# counter_using_CD4026BE.net
KiCad netlist of a schematic drawn in Altium Designer
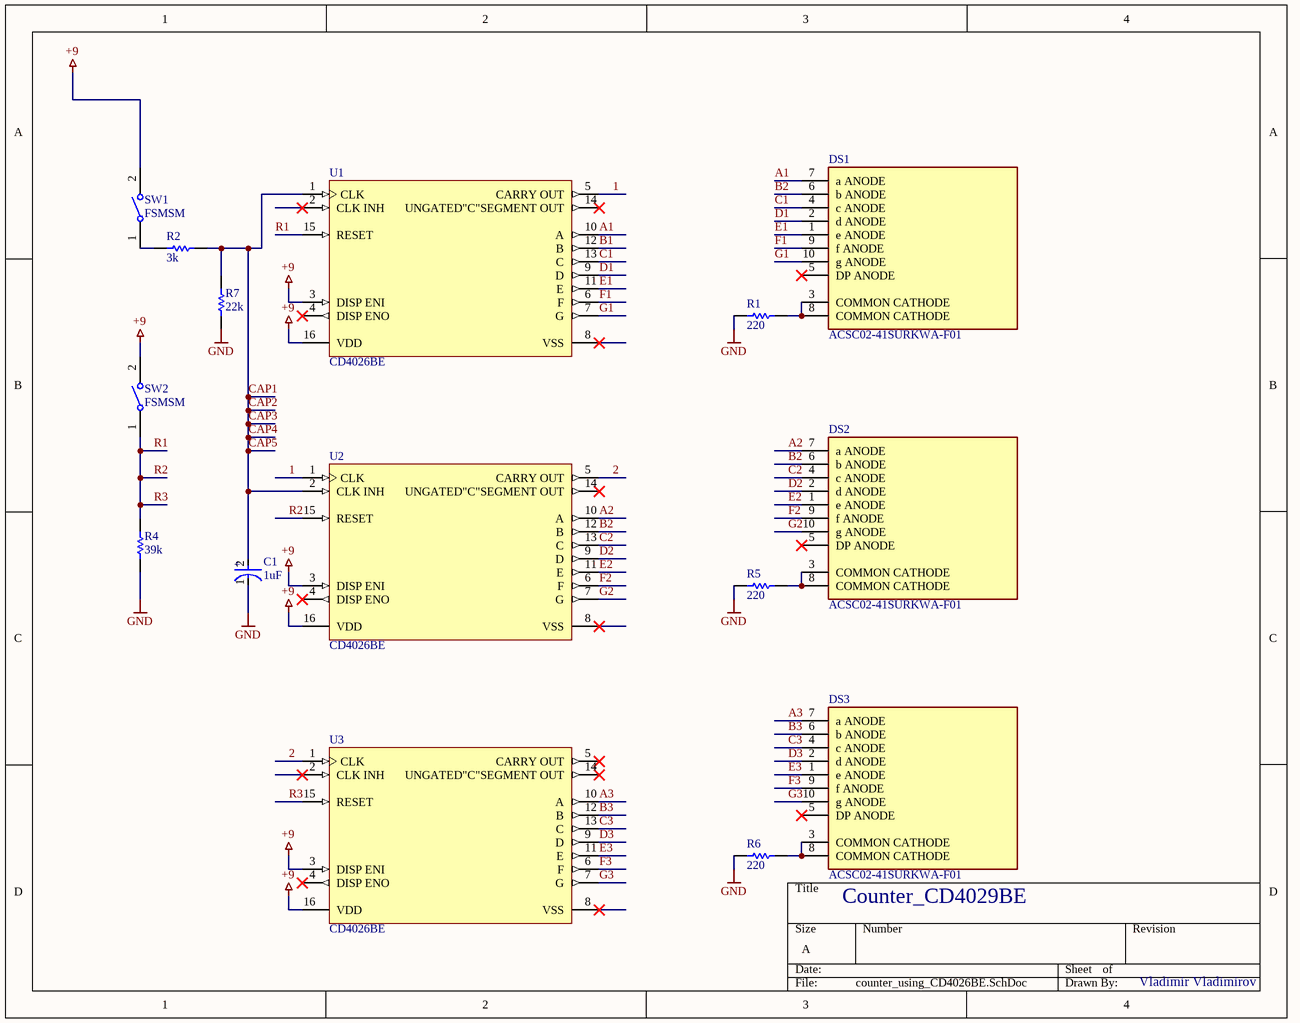
[diagram p0: counter_using_CD4026BE.SchDoc]

(export (version "E")
  (design (tool "Eeschema 10.0.6"))
  (components
    (comp (ref "C1")
      (value "1uF")
      (footprint "FP-FCB-MFG")
      (fields (field (name "TOLERANCE") "20%") (field (name "VOLTAGE") "50V"))
      (libsource (lib "Altium Content Vault") (part "a00bbbee19879c290e62620ae7e47b1"))
    )
    (comp (ref "DS1")
      (value "ACSC02-41SURKWA-F01")
      (footprint "FP-ACSC02-41SURKWA-F01-MFG")
      (description "DISPLAY 7-SEG 0.2\" SGL RED 10SMD")
      (libsource (lib "Altium Content Vault") (part "0e920bf6b93db43d611184977c40d65"))
    )
    (comp (ref "DS2")
      (value "ACSC02-41SURKWA-F01")
      (footprint "FP-ACSC02-41SURKWA-F01-MFG")
      (description "DISPLAY 7-SEG 0.2\" SGL RED 10SMD")
      (libsource (lib "Altium Content Vault") (part "0e920bf6b93db43d611184977c40d65"))
    )
    (comp (ref "DS3")
      (value "ACSC02-41SURKWA-F01")
      (footprint "FP-ACSC02-41SURKWA-F01-MFG")
      (description "DISPLAY 7-SEG 0.2\" SGL RED 10SMD")
      (libsource (lib "Altium Content Vault") (part "0e920bf6b93db43d611184977c40d65"))
    )
    (comp (ref "R1")
      (value "220")
      (footprint "RESC2013X70X40NL20T20")
      (fields (field (name "PART NUMBER") "ERJ6ENF2200V") (field (name "MANUFACTURER") "Panasonic"))
      (libsource (lib "Altium Content Vault") (part "RES"))
    )
    (comp (ref "R2")
      (value "3k")
      (footprint "RESC2013X70X40NL20T20")
      (fields (field (name "PART NUMBER") "ERJ6ENF2200V") (field (name "MANUFACTURER") "Panasonic"))
      (libsource (lib "Altium Content Vault") (part "RES"))
    )
    (comp (ref "R4")
      (value "39k")
      (footprint "RESC2013X70X40NL20T20")
      (fields (field (name "PART NUMBER") "ERJ6ENF2200V") (field (name "MANUFACTURER") "Panasonic"))
      (libsource (lib "Altium Content Vault") (part "RES"))
    )
    (comp (ref "R5")
      (value "220")
      (footprint "RESC2013X70X40NL20T20")
      (fields (field (name "PART NUMBER") "ERJ6ENF2200V") (field (name "MANUFACTURER") "Panasonic"))
      (libsource (lib "Altium Content Vault") (part "RES"))
    )
    (comp (ref "R6")
      (value "220")
      (footprint "RESC2013X70X40NL20T20")
      (fields (field (name "PART NUMBER") "ERJ6ENF2200V") (field (name "MANUFACTURER") "Panasonic"))
      (libsource (lib "Altium Content Vault") (part "RES"))
    )
    (comp (ref "R7")
      (value "22k")
      (footprint "RESC2013X70X40NL20T20")
      (fields (field (name "PART NUMBER") "ERJ6ENF2200V") (field (name "MANUFACTURER") "Panasonic"))
      (libsource (lib "Altium Content Vault") (part "RES"))
    )
    (comp (ref "SW1")
      (value "FSMSM")
      (footprint "TECO-FSMSM-2_V")
      (description "FSMSM Push Button Switch, 50 mA, -35 to 85 degC, 2-Pin SMD, RoHS, Bulk")
      (fields (field (name "MANUFACTURER") "TE Connectivity"))
      (libsource (lib "Altium Content Vault") (part "SW-SPST-2_C"))
    )
    (comp (ref "SW2")
      (value "FSMSM")
      (footprint "TECO-FSMSM-2_V")
      (description "FSMSM Push Button Switch, 50 mA, -35 to 85 degC, 2-Pin SMD, RoHS, Bulk")
      (fields (field (name "MANUFACTURER") "TE Connectivity"))
      (libsource (lib "Altium Content Vault") (part "SW-SPST-2_C"))
    )
    (comp (ref "U1")
      (value "CD4026BE")
      (footprint "N0016A")
      (fields
        (field (name "MANUFACTURER") "Texas Instruments")
        (field (name "GENERIC PART NUMBER") "CD4026B")
      )
      (libsource (lib "Altium Content Vault") (part "TI-CD4026B-16"))
    )
    (comp (ref "U2")
      (value "CD4026BE")
      (footprint "N0016A")
      (fields
        (field (name "MANUFACTURER") "Texas Instruments")
        (field (name "GENERIC PART NUMBER") "CD4026B")
      )
      (libsource (lib "Altium Content Vault") (part "TI-CD4026B-16"))
    )
    (comp (ref "U3")
      (value "CD4026BE")
      (footprint "N0016A")
      (fields
        (field (name "MANUFACTURER") "Texas Instruments")
        (field (name "GENERIC PART NUMBER") "CD4026B")
      )
      (libsource (lib "Altium Content Vault") (part "TI-CD4026B-16"))
    )
  )
  (nets
    (net (code "1") (name "+9") (class "Default")
      (node (ref "SW1") (pin "2") (pinfunction "2_2") (pintype "passive"))
      (node (ref "SW2") (pin "2") (pinfunction "2_2") (pintype "passive"))
      (node (ref "U1") (pin "16") (pinfunction "VDD_16") (pintype "power_in"))
      (node (ref "U1") (pin "3") (pinfunction "DISP_ENI_3") (pintype "input"))
      (node (ref "U2") (pin "16") (pinfunction "VDD_16") (pintype "power_in"))
      (node (ref "U2") (pin "3") (pinfunction "DISP_ENI_3") (pintype "input"))
      (node (ref "U3") (pin "16") (pinfunction "VDD_16") (pintype "power_in"))
      (node (ref "U3") (pin "3") (pinfunction "DISP_ENI_3") (pintype "input"))
    )
    (net (code "2") (name "/1") (class "Default")
      (node (ref "U1") (pin "5") (pinfunction "CARRY_OUT_5") (pintype "output"))
      (node (ref "U2") (pin "1") (pinfunction "CLK_1") (pintype "input"))
    )
    (net (code "3") (name "/2") (class "Default")
      (node (ref "U2") (pin "5") (pinfunction "CARRY_OUT_5") (pintype "output"))
      (node (ref "U3") (pin "1") (pinfunction "CLK_1") (pintype "input"))
    )
    (net (code "4") (name "/A1") (class "Default")
      (node (ref "DS1") (pin "7") (pinfunction "a_ANODE_7") (pintype "passive"))
      (node (ref "U1") (pin "10") (pinfunction "A_10") (pintype "output"))
    )
    (net (code "5") (name "/A2") (class "Default")
      (node (ref "DS2") (pin "7") (pinfunction "a_ANODE_7") (pintype "passive"))
      (node (ref "U2") (pin "10") (pinfunction "A_10") (pintype "output"))
    )
    (net (code "6") (name "/A3") (class "Default")
      (node (ref "DS3") (pin "7") (pinfunction "a_ANODE_7") (pintype "passive"))
      (node (ref "U3") (pin "10") (pinfunction "A_10") (pintype "output"))
    )
    (net (code "7") (name "/B1") (class "Default")
      (node (ref "U1") (pin "12") (pinfunction "B_12") (pintype "output"))
    )
    (net (code "8") (name "/B2") (class "Default")
      (node (ref "DS1") (pin "6") (pinfunction "b_ANODE_6") (pintype "passive"))
      (node (ref "DS2") (pin "6") (pinfunction "b_ANODE_6") (pintype "passive"))
      (node (ref "U2") (pin "12") (pinfunction "B_12") (pintype "output"))
    )
    (net (code "9") (name "/B3") (class "Default")
      (node (ref "DS3") (pin "6") (pinfunction "b_ANODE_6") (pintype "passive"))
      (node (ref "U3") (pin "12") (pinfunction "B_12") (pintype "output"))
    )
    (net (code "10") (name "/C1") (class "Default")
      (node (ref "DS1") (pin "4") (pinfunction "c_ANODE_4") (pintype "passive"))
      (node (ref "U1") (pin "13") (pinfunction "C_13") (pintype "output"))
    )
    (net (code "11") (name "/C2") (class "Default")
      (node (ref "DS2") (pin "4") (pinfunction "c_ANODE_4") (pintype "passive"))
      (node (ref "U2") (pin "13") (pinfunction "C_13") (pintype "output"))
    )
    (net (code "12") (name "/C3") (class "Default")
      (node (ref "DS3") (pin "4") (pinfunction "c_ANODE_4") (pintype "passive"))
      (node (ref "U3") (pin "13") (pinfunction "C_13") (pintype "output"))
    )
    (net (code "13") (name "/CAP1") (class "Default")
      (node (ref "C1") (pin "2") (pinfunction "A_2") (pintype "passive"))
      (node (ref "R2") (pin "2") (pinfunction "2_2") (pintype "passive"))
      (node (ref "R7") (pin "2") (pinfunction "2_2") (pintype "passive"))
      (node (ref "U1") (pin "1") (pinfunction "CLK_1") (pintype "input"))
      (node (ref "U2") (pin "2") (pinfunction "CLK_INH_2") (pintype "input"))
    )
    (net (code "14") (name "/D1") (class "Default")
      (node (ref "DS1") (pin "2") (pinfunction "d_ANODE_2") (pintype "passive"))
      (node (ref "U1") (pin "9") (pinfunction "D_9") (pintype "output"))
    )
    (net (code "15") (name "/D2") (class "Default")
      (node (ref "DS2") (pin "2") (pinfunction "d_ANODE_2") (pintype "passive"))
      (node (ref "U2") (pin "9") (pinfunction "D_9") (pintype "output"))
    )
    (net (code "16") (name "/D3") (class "Default")
      (node (ref "DS3") (pin "2") (pinfunction "d_ANODE_2") (pintype "passive"))
      (node (ref "U3") (pin "9") (pinfunction "D_9") (pintype "output"))
    )
    (net (code "17") (name "/E1") (class "Default")
      (node (ref "DS1") (pin "1") (pinfunction "e_ANODE_1") (pintype "passive"))
      (node (ref "U1") (pin "11") (pinfunction "E_11") (pintype "output"))
    )
    (net (code "18") (name "/E2") (class "Default")
      (node (ref "DS2") (pin "1") (pinfunction "e_ANODE_1") (pintype "passive"))
      (node (ref "U2") (pin "11") (pinfunction "E_11") (pintype "output"))
    )
    (net (code "19") (name "/E3") (class "Default")
      (node (ref "DS3") (pin "1") (pinfunction "e_ANODE_1") (pintype "passive"))
      (node (ref "U3") (pin "11") (pinfunction "E_11") (pintype "output"))
    )
    (net (code "20") (name "/F1") (class "Default")
      (node (ref "DS1") (pin "9") (pinfunction "f_ANODE_9") (pintype "passive"))
      (node (ref "U1") (pin "6") (pinfunction "F_6") (pintype "output"))
    )
    (net (code "21") (name "/F2") (class "Default")
      (node (ref "DS2") (pin "9") (pinfunction "f_ANODE_9") (pintype "passive"))
      (node (ref "U2") (pin "6") (pinfunction "F_6") (pintype "output"))
    )
    (net (code "22") (name "/F3") (class "Default")
      (node (ref "DS3") (pin "9") (pinfunction "f_ANODE_9") (pintype "passive"))
      (node (ref "U3") (pin "6") (pinfunction "F_6") (pintype "output"))
    )
    (net (code "23") (name "/G1") (class "Default")
      (node (ref "DS1") (pin "10") (pinfunction "g_ANODE_10") (pintype "passive"))
      (node (ref "U1") (pin "7") (pinfunction "G_7") (pintype "output"))
    )
    (net (code "24") (name "/G2") (class "Default")
      (node (ref "DS2") (pin "10") (pinfunction "g_ANODE_10") (pintype "passive"))
      (node (ref "U2") (pin "7") (pinfunction "G_7") (pintype "output"))
    )
    (net (code "25") (name "/G3") (class "Default")
      (node (ref "DS3") (pin "10") (pinfunction "g_ANODE_10") (pintype "passive"))
      (node (ref "U3") (pin "7") (pinfunction "G_7") (pintype "output"))
    )
    (net (code "26") (name "/R1") (class "Default")
      (node (ref "R4") (pin "2") (pinfunction "2_2") (pintype "passive"))
      (node (ref "SW2") (pin "1") (pinfunction "1_1") (pintype "passive"))
      (node (ref "U1") (pin "15") (pinfunction "RESET_15") (pintype "input"))
      (node (ref "U2") (pin "15") (pinfunction "RESET_15") (pintype "input"))
      (node (ref "U3") (pin "15") (pinfunction "RESET_15") (pintype "input"))
    )
    (net (code "27") (name "GND") (class "Default")
      (node (ref "C1") (pin "1") (pinfunction "C_1") (pintype "passive"))
      (node (ref "R1") (pin "1") (pinfunction "1_1") (pintype "passive"))
      (node (ref "R4") (pin "1") (pinfunction "1_1") (pintype "passive"))
      (node (ref "R5") (pin "2") (pinfunction "2_2") (pintype "passive"))
      (node (ref "R6") (pin "2") (pinfunction "2_2") (pintype "passive"))
      (node (ref "R7") (pin "1") (pinfunction "1_1") (pintype "passive"))
    )
    (net (code "28") (name "Net-(DS1-COMMON_CATHODE-Pad3)") (class "Default")
      (node (ref "DS1") (pin "3") (pinfunction "COMMON_CATHODE_3") (pintype "passive"))
      (node (ref "DS1") (pin "8") (pinfunction "COMMON_CATHODE_8") (pintype "passive"))
      (node (ref "R1") (pin "2") (pinfunction "2_2") (pintype "passive"))
    )
    (net (code "29") (name "Net-(DS2-COMMON_CATHODE-Pad3)") (class "Default")
      (node (ref "DS2") (pin "3") (pinfunction "COMMON_CATHODE_3") (pintype "passive"))
      (node (ref "DS2") (pin "8") (pinfunction "COMMON_CATHODE_8") (pintype "passive"))
      (node (ref "R5") (pin "1") (pinfunction "1_1") (pintype "passive"))
    )
    (net (code "30") (name "Net-(DS3-COMMON_CATHODE-Pad3)") (class "Default")
      (node (ref "DS3") (pin "3") (pinfunction "COMMON_CATHODE_3") (pintype "passive"))
      (node (ref "DS3") (pin "8") (pinfunction "COMMON_CATHODE_8") (pintype "passive"))
      (node (ref "R6") (pin "1") (pinfunction "1_1") (pintype "passive"))
    )
    (net (code "31") (name "Net-(R2-Pad1)") (class "Default")
      (node (ref "R2") (pin "1") (pinfunction "1_1") (pintype "passive"))
      (node (ref "SW1") (pin "1") (pinfunction "1_1") (pintype "passive"))
    )
    (net (code "32") (name "unconnected-(DS1-DP_ANODE-Pad5)") (class "Default")
      (node (ref "DS1") (pin "5") (pinfunction "DP_ANODE_5") (pintype "passive+no_connect"))
    )
    (net (code "33") (name "unconnected-(DS2-DP_ANODE-Pad5)") (class "Default")
      (node (ref "DS2") (pin "5") (pinfunction "DP_ANODE_5") (pintype "passive+no_connect"))
    )
    (net (code "34") (name "unconnected-(DS3-DP_ANODE-Pad5)") (class "Default")
      (node (ref "DS3") (pin "5") (pinfunction "DP_ANODE_5") (pintype "passive+no_connect"))
    )
    (net (code "35") (name "unconnected-(U1-CLK_INH-Pad2)") (class "Default")
      (node (ref "U1") (pin "2") (pinfunction "CLK_INH_2") (pintype "input+no_connect"))
    )
    (net (code "36") (name "unconnected-(U1-DISP_ENO-Pad4)") (class "Default")
      (node (ref "U1") (pin "4") (pinfunction "DISP_ENO_4") (pintype "output+no_connect"))
    )
    (net (code "37") (name "unconnected-(U1-UNGATED\"C\"SEGMENT_OUT-Pad14)") (class "Default")
      (node (ref "U1") (pin "14") (pinfunction "UNGATED\"C\"SEGMENT_OUT_14") (pintype "output+no_connect"))
    )
    (net (code "38") (name "unconnected-(U1-VSS-Pad8)") (class "Default")
      (node (ref "U1") (pin "8") (pinfunction "VSS_8") (pintype "power_in+no_connect"))
    )
    (net (code "39") (name "unconnected-(U2-DISP_ENO-Pad4)") (class "Default")
      (node (ref "U2") (pin "4") (pinfunction "DISP_ENO_4") (pintype "output+no_connect"))
    )
    (net (code "40") (name "unconnected-(U2-UNGATED\"C\"SEGMENT_OUT-Pad14)") (class "Default")
      (node (ref "U2") (pin "14") (pinfunction "UNGATED\"C\"SEGMENT_OUT_14") (pintype "output+no_connect"))
    )
    (net (code "41") (name "unconnected-(U2-VSS-Pad8)") (class "Default")
      (node (ref "U2") (pin "8") (pinfunction "VSS_8") (pintype "power_in+no_connect"))
    )
    (net (code "42") (name "unconnected-(U3-CARRY_OUT-Pad5)") (class "Default")
      (node (ref "U3") (pin "5") (pinfunction "CARRY_OUT_5") (pintype "output+no_connect"))
    )
    (net (code "43") (name "unconnected-(U3-CLK_INH-Pad2)") (class "Default")
      (node (ref "U3") (pin "2") (pinfunction "CLK_INH_2") (pintype "input+no_connect"))
    )
    (net (code "44") (name "unconnected-(U3-DISP_ENO-Pad4)") (class "Default")
      (node (ref "U3") (pin "4") (pinfunction "DISP_ENO_4") (pintype "output+no_connect"))
    )
    (net (code "45") (name "unconnected-(U3-UNGATED\"C\"SEGMENT_OUT-Pad14)") (class "Default")
      (node (ref "U3") (pin "14") (pinfunction "UNGATED\"C\"SEGMENT_OUT_14") (pintype "output+no_connect"))
    )
    (net (code "46") (name "unconnected-(U3-VSS-Pad8)") (class "Default")
      (node (ref "U3") (pin "8") (pinfunction "VSS_8") (pintype "power_in+no_connect"))
    )
  )
)
